# Adafruit_Si5351A.net
KiCad netlist of a schematic drawn in EAGLE
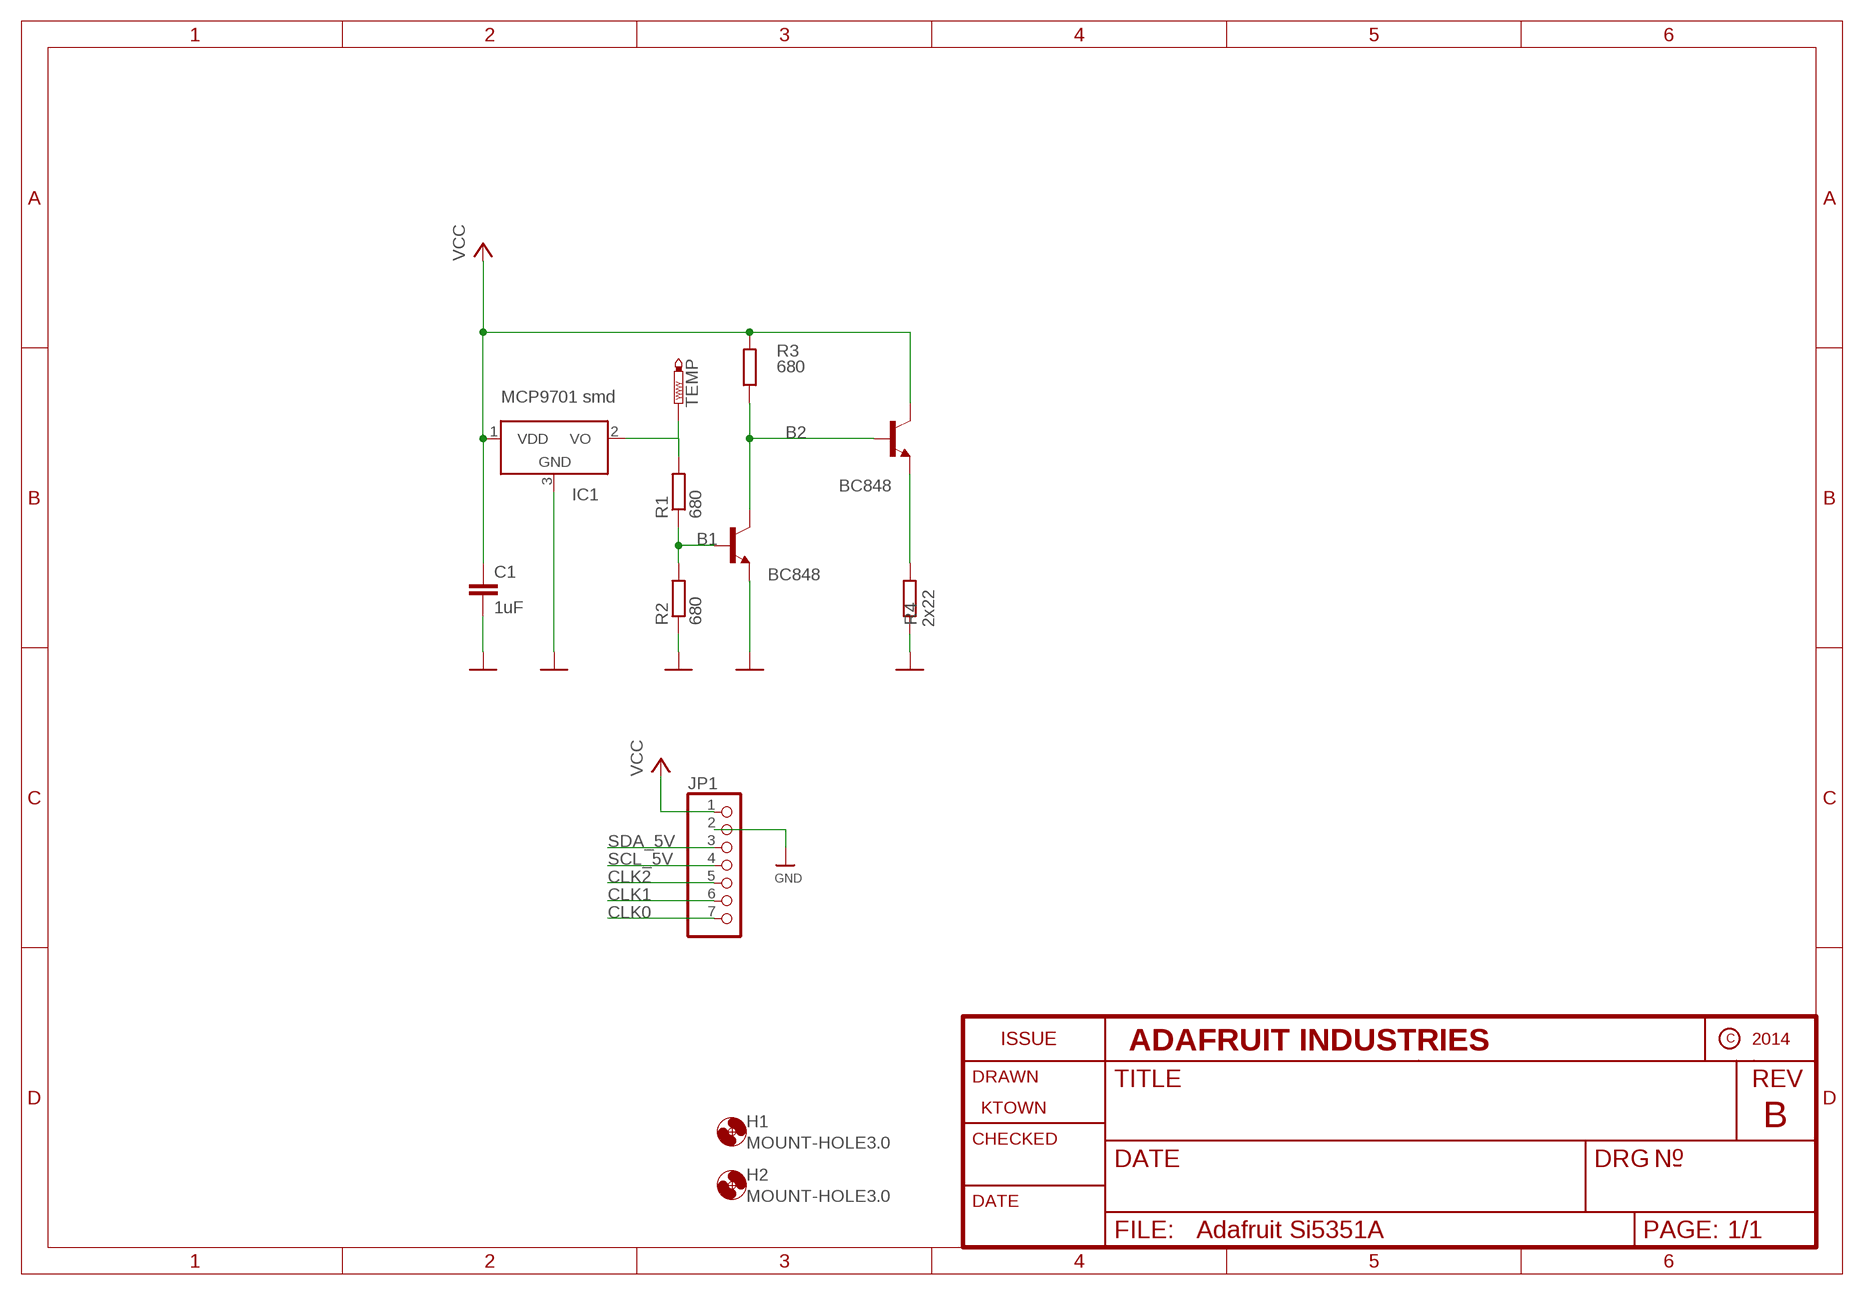
[diagram p0: schematic, sheet 1]

(export (version "E")
  (design (tool "Eeschema 10.0.6"))
  (components
    (comp (ref "C1")
      (value "1uF")
      (footprint "eagle-import:C1210")
      (libsource (lib "eagle-import") (part "CAPX5R"))
    )
    (comp (ref "H1")
      (value "MOUNT-HOLE3.0")
      (footprint "eagle-import:3,0")
      (libsource (lib "eagle-import") (part "MOUNT-HOLE3.0"))
    )
    (comp (ref "H2")
      (value "MOUNT-HOLE3.0")
      (footprint "eagle-import:3,0")
      (libsource (lib "eagle-import") (part "MOUNT-HOLE3.0"))
    )
    (comp (ref "IC1")
      (value "MCP9701 smd")
      (footprint "eagle-import:SOT23-3")
      (libsource (lib "eagle-import") (part "MCP9700T"))
    )
    (comp (ref "JP1")
      (value "HEADER-1X7THICKER")
      (footprint "eagle-import:1X07_ROUND_76")
      (libsource (lib "eagle-import") (part "HEADER-1X7THICKER"))
    )
    (comp (ref "R1")
      (value "680")
      (footprint "eagle-import:M1206")
      (libsource (lib "eagle-import") (part "R-EU_M1206"))
    )
    (comp (ref "R2")
      (value "680")
      (footprint "eagle-import:M1206")
      (libsource (lib "eagle-import") (part "R-EU_M1206"))
    )
    (comp (ref "R3")
      (value "680")
      (footprint "eagle-import:M1206")
      (libsource (lib "eagle-import") (part "R-EU_M1206"))
    )
    (comp (ref "R4")
      (value "2x22")
      (footprint "eagle-import:M1206")
      (libsource (lib "eagle-import") (part "R-EU_M1206"))
    )
    (comp (ref "T1")
      (value "BC848")
      (footprint "eagle-import:SOT23")
      (libsource (lib "eagle-import") (part "BC848"))
    )
    (comp (ref "T2")
      (value "BC848")
      (footprint "eagle-import:SOT23")
      (libsource (lib "eagle-import") (part "BC848"))
    )
    (comp (ref "TEMP")
      (value "PTR1TP10SQ")
      (footprint "eagle-import:TP10SQ")
      (libsource (lib "eagle-import") (part "PTR1TP10SQ"))
    )
  )
  (nets
    (net (code "1") (name "/B1") (class "Default")
      (node (ref "R1") (pin "1") (pinfunction "1_1") (pintype "passive"))
      (node (ref "R2") (pin "2") (pinfunction "2_2") (pintype "passive"))
      (node (ref "T1") (pin "1") (pinfunction "B_1") (pintype "passive"))
    )
    (net (code "2") (name "/B2") (class "Default")
      (node (ref "R3") (pin "1") (pinfunction "1_1") (pintype "passive"))
      (node (ref "T1") (pin "3") (pinfunction "C_3") (pintype "passive"))
      (node (ref "T2") (pin "1") (pinfunction "B_1") (pintype "passive"))
    )
    (net (code "3") (name "/CLK0") (class "Default")
      (node (ref "JP1") (pin "7") (pinfunction "7_7") (pintype "passive"))
    )
    (net (code "4") (name "/CLK1") (class "Default")
      (node (ref "JP1") (pin "6") (pinfunction "6_6") (pintype "passive"))
    )
    (net (code "5") (name "/CLK2") (class "Default")
      (node (ref "JP1") (pin "5") (pinfunction "5_5") (pintype "passive"))
    )
    (net (code "6") (name "/SCL_5V") (class "Default")
      (node (ref "JP1") (pin "4") (pinfunction "4_4") (pintype "passive"))
    )
    (net (code "7") (name "/SDA_5V") (class "Default")
      (node (ref "JP1") (pin "3") (pinfunction "3_3") (pintype "passive"))
    )
    (net (code "8") (name "GND") (class "Default")
      (node (ref "C1") (pin "2") (pinfunction "2_2") (pintype "passive"))
      (node (ref "IC1") (pin "3") (pinfunction "GND_3") (pintype "power_in"))
      (node (ref "JP1") (pin "2") (pinfunction "2_2") (pintype "passive"))
      (node (ref "R2") (pin "1") (pinfunction "1_1") (pintype "passive"))
      (node (ref "R4") (pin "1") (pinfunction "1_1") (pintype "passive"))
      (node (ref "T1") (pin "2") (pinfunction "E_2") (pintype "passive"))
    )
    (net (code "9") (name "Net-(IC1-VO)") (class "Default")
      (node (ref "IC1") (pin "2") (pinfunction "VO_2") (pintype "bidirectional"))
      (node (ref "R1") (pin "2") (pinfunction "2_2") (pintype "passive"))
      (node (ref "TEMP") (pin "TP") (pinfunction "TP_TP") (pintype "input"))
    )
    (net (code "10") (name "Net-(T2-E)") (class "Default")
      (node (ref "R4") (pin "2") (pinfunction "2_2") (pintype "passive"))
      (node (ref "T2") (pin "2") (pinfunction "E_2") (pintype "passive"))
    )
    (net (code "11") (name "VCC") (class "Default")
      (node (ref "C1") (pin "1") (pinfunction "1_1") (pintype "passive"))
      (node (ref "IC1") (pin "1") (pinfunction "VDD_1") (pintype "power_in"))
      (node (ref "JP1") (pin "1") (pinfunction "1_1") (pintype "passive"))
      (node (ref "R3") (pin "2") (pinfunction "2_2") (pintype "passive"))
      (node (ref "T2") (pin "3") (pinfunction "C_3") (pintype "passive"))
    )
  )
)
